# 3_-_STM32F103_Debugger.net
KiCad netlist of a schematic drawn in Altium Designer
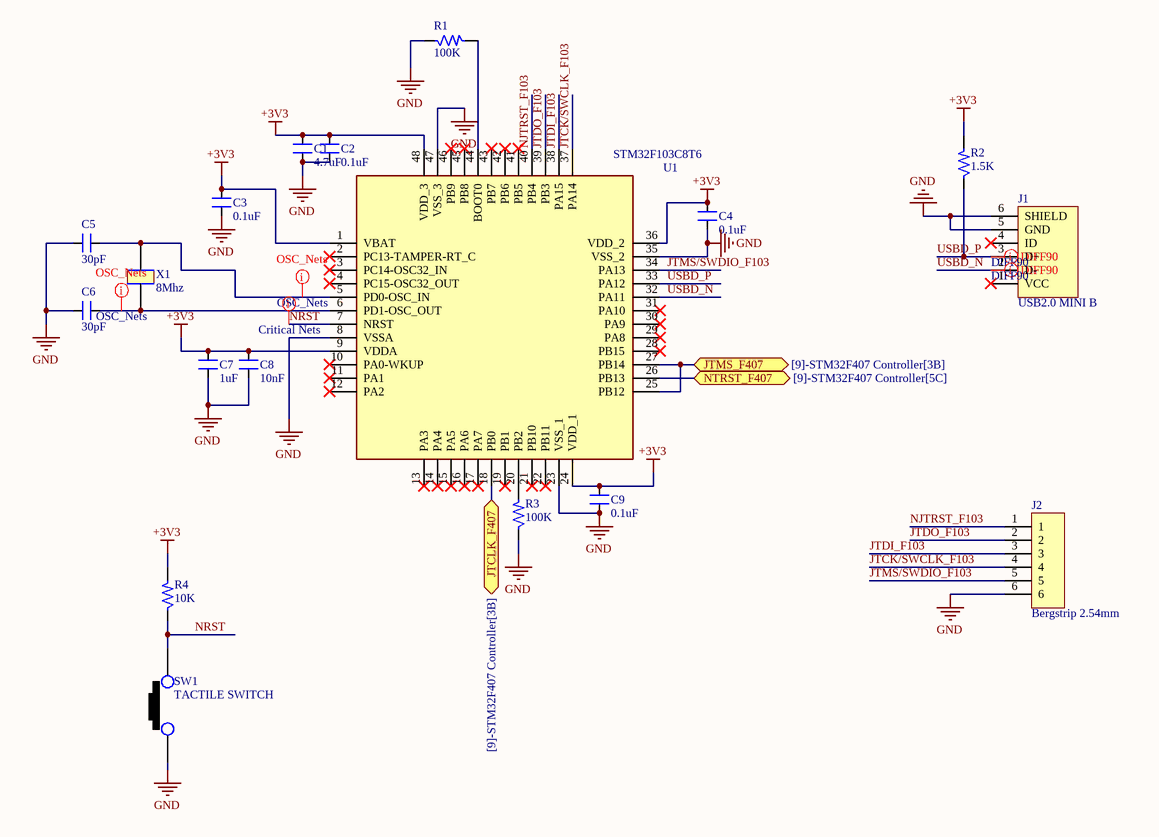
[diagram p0: [3]- STM32F103 Debugger.SchDoc]

(export (version "E")
  (design (tool "Eeschema 10.0.6"))
  (components
    (comp (ref "C1")
      (value "4.7uF")
      (footprint "CAP_0805")
      (description "4.7µF ±10% 50V Ceramic Capacitor X5R 0805 (2012 Metric)")
      (fields
        (field (name "MANUFACTURER") "Yageo")
        (field (name "MANUFACTURER PART NUMBER") "GRM21BR61H475KE51L")
      )
      (libsource (lib "ESTEEMPCBLIB") (part "CAP_4.7uF-50V-10%-0805"))
    )
    (comp (ref "C2")
      (value "0.1uF")
      (footprint "CAP_0805")
      (description "0.1µF ±10% 50V Ceramic Capacitor X7R 0805 (2012 Metric)")
      (fields
        (field (name "MANUFACTURER") "Samsung")
        (field (name "MANUFACTURER PART NUMBER") "CL21B104KBCNNNC")
      )
      (libsource (lib "ESTEEMPCBLIB") (part "CAP_0.1uF-50V-10%-0805"))
    )
    (comp (ref "C3")
      (value "0.1uF")
      (footprint "CAP_0805")
      (description "0.1µF ±10% 50V Ceramic Capacitor X7R 0805 (2012 Metric)")
      (fields
        (field (name "MANUFACTURER") "Samsung")
        (field (name "MANUFACTURER PART NUMBER") "CL21B104KBCNNNC")
      )
      (libsource (lib "ESTEEMPCBLIB") (part "CAP_0.1uF-50V-10%-0805"))
    )
    (comp (ref "C4")
      (value "0.1uF")
      (footprint "CAP_0805")
      (description "0.1µF ±10% 50V Ceramic Capacitor X7R 0805 (2012 Metric)")
      (fields
        (field (name "MANUFACTURER") "Samsung")
        (field (name "MANUFACTURER PART NUMBER") "CL21B104KBCNNNC")
      )
      (libsource (lib "ESTEEMPCBLIB") (part "CAP_0.1uF-50V-10%-0805"))
    )
    (comp (ref "C5")
      (value "30pF")
      (footprint "CAP_0805")
      (description "±10% 50V Ceramic Capacitor C0G, NP0 0805 (2012 Metric)")
      (fields
        (field (name "MANUFACTURER PART NUMBER") "C0805C300K5GAC7800")
        (field (name "MANUFACTURER") "KEMET")
      )
      (libsource (lib "ESTEEMPCBLIB") (part "CAP_30pF-50V-10%-0805"))
    )
    (comp (ref "C6")
      (value "30pF")
      (footprint "CAP_0805")
      (description "±10% 50V Ceramic Capacitor C0G, NP0 0805 (2012 Metric)")
      (fields
        (field (name "MANUFACTURER PART NUMBER") "C0805C300K5GAC7800")
        (field (name "MANUFACTURER") "KEMET")
      )
      (libsource (lib "ESTEEMPCBLIB") (part "CAP_30pF-50V-10%-0805"))
    )
    (comp (ref "C7")
      (value "1uF")
      (footprint "CAP_0805")
      (description "1µF ±5% 50V Ceramic Capacitor X7R 0805 (2012 Metric)")
      (fields
        (field (name "MANUFACTURER") "Samsung")
        (field (name "MANUFACTURER PART NUMBER") "CC0805JKX7R9BB105")
      )
      (libsource (lib "ESTEEMPCBLIB") (part "CAP_1uF-50V-5%-0805"))
    )
    (comp (ref "C8")
      (value "10nF")
      (footprint "CAP_0805")
      (description "10000pF ±10% 50V Ceramic Capacitor X7R 0805 (2012 Metric)")
      (fields
        (field (name "MANUFACTURER") "Samsung")
        (field (name "MANUFACTURER PART NUMBER") "C0805C103K5RECAUTO")
      )
      (libsource (lib "ESTEEMPCBLIB") (part "CAP_10nF-50V-10%-0805"))
    )
    (comp (ref "C9")
      (value "0.1uF")
      (footprint "CAP_0805")
      (description "0.1µF ±10% 50V Ceramic Capacitor X7R 0805 (2012 Metric)")
      (fields
        (field (name "MANUFACTURER") "Samsung")
        (field (name "MANUFACTURER PART NUMBER") "CL21B104KBCNNNC")
      )
      (libsource (lib "ESTEEMPCBLIB") (part "CAP_0.1uF-50V-10%-0805"))
    )
    (comp (ref "J1")
      (value "USB2.0 MINI B")
      (footprint "CON_690-005-299-043")
      (description "USB - mini B USB 2.0 Receptacle Connector 5 Position Surface Mount, Right Angle")
      (fields
        (field (name "MANUFACTURER") "EDAC")
        (field (name "MANUFACTURER PART NUMBER") "690-005-299-043")
      )
      (libsource (lib "ESTEEMPCBLIB") (part "CON_USB2.0-MINIB-SMD"))
    )
    (comp (ref "J2")
      (value "Bergstrip 2.54mm")
      (footprint "CON6_100_59D78_TH_ST")
      (description "6 Pins, 1 Row 2.54mm Pitch, Straight bergstrip, Female")
      (fields (field (name "MANUFACTURER") "Molex") (field (name "MANUFACTURER PART NUMBER") "22-10-2061"))
      (libsource (lib "ESTEEMPCBLIB") (part "CON-BS-SKT_6X1-100-ST-TH"))
    )
    (comp (ref "R1")
      (value "100K")
      (footprint "RES_0603")
      (description "100 kOhms ±1% 0.1W, 1/10W Chip Resistor 0603 (1608 Metric) Automotive AEC-Q200 Thick Film")
      (fields
        (field (name "MANUFACTURER") "Stackpole Electronics")
        (field (name "MANUFACTURER PART NUMBER") "RMCF0603FT100K")
      )
      (libsource (lib "ESTEEMPCBLIB") (part "RES_100K-0.1W-1%-0603"))
    )
    (comp (ref "R2")
      (value "1.5K")
      (footprint "RES_0805")
      (description "1.5 kOhms ±1% 0.125W, 1/8W Chip Resistor 0805 (2012 Metric) Thick Film")
      (fields
        (field (name "MANUFACTURER") "TE Connectivity Passive Product")
        (field (name "MANUFACTURER PART NUMBER") "CRG0805F1K5")
      )
      (libsource (lib "ESTEEMPCBLIB") (part "RES_1.5K-0.125W-1%-0805"))
    )
    (comp (ref "R3")
      (value "100K")
      (footprint "RES_0603")
      (description "100 kOhms ±1% 0.1W, 1/10W Chip Resistor 0603 (1608 Metric) Automotive AEC-Q200 Thick Film")
      (fields
        (field (name "MANUFACTURER") "Stackpole Electronics")
        (field (name "MANUFACTURER PART NUMBER") "RMCF0603FT100K")
      )
      (libsource (lib "ESTEEMPCBLIB") (part "RES_100K-0.1W-1%-0603"))
    )
    (comp (ref "R4")
      (value "10K")
      (footprint "RES_0603")
      (description "10 kOhms ±1% 0.1W, 1/10W Chip Resistor 0603 (1608 Metric) Automotive AEC-Q200 Thick Film")
      (fields (field (name "MANUFACTURER") "Walsin") (field (name "MANUFACTURER PART NUMBER") "WR06X1002FTL"))
      (libsource (lib "ESTEEMPCBLIB") (part "RES_10K-0.1W-1%-0603"))
    )
    (comp (ref "SW1")
      (value "TACTILE SWITCH")
      (footprint "SW_342_SMD")
      (description "Tactile Switch SPST-NO Top Actuated Surface Mount")
      (fields
        (field (name "MANUFACTURER") "ITT C&K")
        (field (name "MANUFACTURER PART NUMBER") "RS-282G05A3-SMRT")
      )
      (libsource (lib "ESTEEMPCBLIB") (part "SW1_RS-282G05A3-SMRT-SMD"))
    )
    (comp (ref "U1")
      (value "STM32F103C8T6")
      (footprint "LQFP-48_19.6_393_58X11_SMD")
      (description "ARM® Cortex®-M3 STM32F1 Microcontroller IC 32-Bit 72MHz 64KB (64K x 8) FLASH 48-LQFP (7x7)")
      (fields (field (name "MANUFACTURER") "STMicroelectronics"))
      (libsource (lib "ESTEEMPCBLIB") (part "IC_STM32F103C8T6"))
    )
    (comp (ref "X1")
      (value "8Mhz")
      (footprint "XTAL_314_240X47_SMD")
      (description "8MHz ±30ppm Crystal 32pF 60 Ohms HC-49/US")
      (fields
        (field (name "MANUFACTURER") "Fox Electronics")
        (field (name "MANUFACTURER PART NUMBER") "ECS-80-32-5PX-TR")
      )
      (libsource (lib "ESTEEMPCBLIB") (part "XTAL_8MHZ-ECS-80-32-5PX-SMD"))
    )
  )
  (nets
    (net (code "1") (name "+3V3") (class "Default")
      (node (ref "C1") (pin "2") (pinfunction "2_2") (pintype "passive"))
      (node (ref "C2") (pin "1") (pinfunction "1_1") (pintype "passive"))
      (node (ref "C3") (pin "2") (pinfunction "2_2") (pintype "passive"))
      (node (ref "C4") (pin "1") (pinfunction "1_1") (pintype "passive"))
      (node (ref "C7") (pin "2") (pinfunction "2_2") (pintype "passive"))
      (node (ref "C8") (pin "2") (pinfunction "2_2") (pintype "passive"))
      (node (ref "C9") (pin "2") (pinfunction "2_2") (pintype "passive"))
      (node (ref "R2") (pin "2") (pinfunction "2_2") (pintype "passive"))
      (node (ref "R4") (pin "2") (pinfunction "2_2") (pintype "passive"))
      (node (ref "U1") (pin "1") (pinfunction "VBAT_1") (pintype "passive"))
      (node (ref "U1") (pin "24") (pinfunction "VDD_1_24") (pintype "passive"))
      (node (ref "U1") (pin "36") (pinfunction "VDD_2_36") (pintype "passive"))
      (node (ref "U1") (pin "48") (pinfunction "VDD_3_48") (pintype "passive"))
      (node (ref "U1") (pin "9") (pinfunction "VDDA_9") (pintype "passive"))
    )
    (net (code "2") (name "/JTCK{slash}SWCLK_F103") (class "Default")
      (node (ref "J2") (pin "4") (pinfunction "4_4") (pintype "passive"))
      (node (ref "U1") (pin "37") (pinfunction "PA14_37") (pintype "passive"))
    )
    (net (code "3") (name "/JTCLK_F407") (class "Default")
      (node (ref "U1") (pin "18") (pinfunction "PB0_18") (pintype "passive"))
    )
    (net (code "4") (name "/JTDI_F103") (class "Default")
      (node (ref "J2") (pin "3") (pinfunction "3_3") (pintype "passive"))
      (node (ref "U1") (pin "38") (pinfunction "PA15_38") (pintype "passive"))
    )
    (net (code "5") (name "/JTDO_F103") (class "Default")
      (node (ref "J2") (pin "2") (pinfunction "2_2") (pintype "passive"))
      (node (ref "U1") (pin "39") (pinfunction "PB3_39") (pintype "passive"))
    )
    (net (code "6") (name "/JTMS_F407") (class "Default")
      (node (ref "U1") (pin "25") (pinfunction "PB12_25") (pintype "passive"))
      (node (ref "U1") (pin "27") (pinfunction "PB14_27") (pintype "passive"))
    )
    (net (code "7") (name "/JTMS{slash}SWDIO_F103") (class "Default")
      (node (ref "J2") (pin "5") (pinfunction "5_5") (pintype "passive"))
      (node (ref "U1") (pin "34") (pinfunction "PA13_34") (pintype "passive"))
    )
    (net (code "8") (name "/NJTRST_F103") (class "Default")
      (node (ref "J2") (pin "1") (pinfunction "1_1") (pintype "passive"))
      (node (ref "U1") (pin "40") (pinfunction "PB4_40") (pintype "passive"))
    )
    (net (code "9") (name "/NRST") (class "Default")
      (node (ref "R4") (pin "1") (pinfunction "1_1") (pintype "passive"))
      (node (ref "SW1") (pin "2") (pinfunction "2_2") (pintype "passive"))
      (node (ref "U1") (pin "7") (pinfunction "NRST_7") (pintype "passive"))
    )
    (net (code "10") (name "/NTRST_F407") (class "Default")
      (node (ref "U1") (pin "26") (pinfunction "PB13_26") (pintype "passive"))
    )
    (net (code "11") (name "/USBD_N") (class "Default")
      (node (ref "J1") (pin "2") (pinfunction "D-_2") (pintype "passive"))
      (node (ref "U1") (pin "32") (pinfunction "PA11_32") (pintype "passive"))
    )
    (net (code "12") (name "/USBD_P") (class "Default")
      (node (ref "J1") (pin "3") (pinfunction "D+_3") (pintype "passive"))
      (node (ref "R2") (pin "1") (pinfunction "1_1") (pintype "passive"))
      (node (ref "U1") (pin "33") (pinfunction "PA12_33") (pintype "passive"))
    )
    (net (code "13") (name "GND") (class "Default")
      (node (ref "C1") (pin "1") (pinfunction "1_1") (pintype "passive"))
      (node (ref "C2") (pin "2") (pinfunction "2_2") (pintype "passive"))
      (node (ref "C3") (pin "1") (pinfunction "1_1") (pintype "passive"))
      (node (ref "C4") (pin "2") (pinfunction "2_2") (pintype "passive"))
      (node (ref "C5") (pin "1") (pinfunction "1_1") (pintype "passive"))
      (node (ref "C6") (pin "1") (pinfunction "1_1") (pintype "passive"))
      (node (ref "C7") (pin "1") (pinfunction "1_1") (pintype "passive"))
      (node (ref "C8") (pin "1") (pinfunction "1_1") (pintype "passive"))
      (node (ref "C9") (pin "1") (pinfunction "1_1") (pintype "passive"))
      (node (ref "J1") (pin "5") (pinfunction "GND_5") (pintype "passive"))
      (node (ref "J1") (pin "6") (pinfunction "SHIELD_6") (pintype "passive"))
      (node (ref "J2") (pin "6") (pinfunction "6_6") (pintype "passive"))
      (node (ref "R1") (pin "1") (pinfunction "1_1") (pintype "passive"))
      (node (ref "R3") (pin "1") (pinfunction "1_1") (pintype "passive"))
      (node (ref "SW1") (pin "1") (pinfunction "1_1") (pintype "passive"))
      (node (ref "U1") (pin "23") (pinfunction "VSS_1_23") (pintype "passive"))
      (node (ref "U1") (pin "35") (pinfunction "VSS_2_35") (pintype "passive"))
      (node (ref "U1") (pin "47") (pinfunction "VSS_3_47") (pintype "passive"))
      (node (ref "U1") (pin "8") (pinfunction "VSSA_8") (pintype "passive"))
    )
    (net (code "14") (name "Net-(U1-BOOT0)") (class "Default")
      (node (ref "R1") (pin "2") (pinfunction "2_2") (pintype "passive"))
      (node (ref "U1") (pin "44") (pinfunction "BOOT0_44") (pintype "passive"))
    )
    (net (code "15") (name "Net-(U1-PB2)") (class "Default")
      (node (ref "R3") (pin "2") (pinfunction "2_2") (pintype "passive"))
      (node (ref "U1") (pin "20") (pinfunction "PB2_20") (pintype "passive"))
    )
    (net (code "16") (name "Net-(U1-PD0-OSC_IN)") (class "Default")
      (node (ref "C5") (pin "2") (pinfunction "2_2") (pintype "passive"))
      (node (ref "U1") (pin "5") (pinfunction "PD0-OSC_IN_5") (pintype "passive"))
      (node (ref "X1") (pin "2") (pinfunction "2_2") (pintype "passive"))
    )
    (net (code "17") (name "Net-(U1-PD1-OSC_OUT)") (class "Default")
      (node (ref "C6") (pin "2") (pinfunction "2_2") (pintype "passive"))
      (node (ref "U1") (pin "6") (pinfunction "PD1-OSC_OUT_6") (pintype "passive"))
      (node (ref "X1") (pin "1") (pinfunction "1_1") (pintype "passive"))
    )
    (net (code "18") (name "unconnected-(J1-ID-Pad4)") (class "Default")
      (node (ref "J1") (pin "4") (pinfunction "ID_4") (pintype "passive+no_connect"))
    )
    (net (code "19") (name "unconnected-(J1-VCC-Pad1)") (class "Default")
      (node (ref "J1") (pin "1") (pinfunction "VCC_1") (pintype "passive+no_connect"))
    )
    (net (code "20") (name "unconnected-(U1-PA0-WKUP-Pad10)") (class "Default")
      (node (ref "U1") (pin "10") (pinfunction "PA0-WKUP_10") (pintype "passive+no_connect"))
    )
    (net (code "21") (name "unconnected-(U1-PA1-Pad11)") (class "Default")
      (node (ref "U1") (pin "11") (pinfunction "PA1_11") (pintype "passive+no_connect"))
    )
    (net (code "22") (name "unconnected-(U1-PA2-Pad12)") (class "Default")
      (node (ref "U1") (pin "12") (pinfunction "PA2_12") (pintype "passive+no_connect"))
    )
    (net (code "23") (name "unconnected-(U1-PA3-Pad13)") (class "Default")
      (node (ref "U1") (pin "13") (pinfunction "PA3_13") (pintype "passive+no_connect"))
    )
    (net (code "24") (name "unconnected-(U1-PA4-Pad14)") (class "Default")
      (node (ref "U1") (pin "14") (pinfunction "PA4_14") (pintype "passive+no_connect"))
    )
    (net (code "25") (name "unconnected-(U1-PA5-Pad15)") (class "Default")
      (node (ref "U1") (pin "15") (pinfunction "PA5_15") (pintype "passive+no_connect"))
    )
    (net (code "26") (name "unconnected-(U1-PA6-Pad16)") (class "Default")
      (node (ref "U1") (pin "16") (pinfunction "PA6_16") (pintype "passive+no_connect"))
    )
    (net (code "27") (name "unconnected-(U1-PA7-Pad17)") (class "Default")
      (node (ref "U1") (pin "17") (pinfunction "PA7_17") (pintype "passive+no_connect"))
    )
    (net (code "28") (name "unconnected-(U1-PA8-Pad29)") (class "Default")
      (node (ref "U1") (pin "29") (pinfunction "PA8_29") (pintype "passive+no_connect"))
    )
    (net (code "29") (name "unconnected-(U1-PA9-Pad30)") (class "Default")
      (node (ref "U1") (pin "30") (pinfunction "PA9_30") (pintype "passive+no_connect"))
    )
    (net (code "30") (name "unconnected-(U1-PA10-Pad31)") (class "Default")
      (node (ref "U1") (pin "31") (pinfunction "PA10_31") (pintype "passive+no_connect"))
    )
    (net (code "31") (name "unconnected-(U1-PB1-Pad19)") (class "Default")
      (node (ref "U1") (pin "19") (pinfunction "PB1_19") (pintype "passive+no_connect"))
    )
    (net (code "32") (name "unconnected-(U1-PB5-Pad41)") (class "Default")
      (node (ref "U1") (pin "41") (pinfunction "PB5_41") (pintype "passive+no_connect"))
    )
    (net (code "33") (name "unconnected-(U1-PB6-Pad42)") (class "Default")
      (node (ref "U1") (pin "42") (pinfunction "PB6_42") (pintype "passive+no_connect"))
    )
    (net (code "34") (name "unconnected-(U1-PB7-Pad43)") (class "Default")
      (node (ref "U1") (pin "43") (pinfunction "PB7_43") (pintype "passive+no_connect"))
    )
    (net (code "35") (name "unconnected-(U1-PB8-Pad45)") (class "Default")
      (node (ref "U1") (pin "45") (pinfunction "PB8_45") (pintype "passive+no_connect"))
    )
    (net (code "36") (name "unconnected-(U1-PB9-Pad46)") (class "Default")
      (node (ref "U1") (pin "46") (pinfunction "PB9_46") (pintype "passive+no_connect"))
    )
    (net (code "37") (name "unconnected-(U1-PB10-Pad21)") (class "Default")
      (node (ref "U1") (pin "21") (pinfunction "PB10_21") (pintype "passive+no_connect"))
    )
    (net (code "38") (name "unconnected-(U1-PB11-Pad22)") (class "Default")
      (node (ref "U1") (pin "22") (pinfunction "PB11_22") (pintype "passive+no_connect"))
    )
    (net (code "39") (name "unconnected-(U1-PB15-Pad28)") (class "Default")
      (node (ref "U1") (pin "28") (pinfunction "PB15_28") (pintype "passive+no_connect"))
    )
    (net (code "40") (name "unconnected-(U1-PC13-TAMPER-RT_C-Pad2)") (class "Default")
      (node (ref "U1") (pin "2") (pinfunction "PC13-TAMPER-RT_C_2") (pintype "passive+no_connect"))
    )
    (net (code "41") (name "unconnected-(U1-PC14-OSC32_IN-Pad3)") (class "Default")
      (node (ref "U1") (pin "3") (pinfunction "PC14-OSC32_IN_3") (pintype "passive+no_connect"))
    )
    (net (code "42") (name "unconnected-(U1-PC15-OSC32_OUT-Pad4)") (class "Default")
      (node (ref "U1") (pin "4") (pinfunction "PC15-OSC32_OUT_4") (pintype "passive+no_connect"))
    )
  )
)
